# connector_valve.net
KiCad netlist of a schematic drawn in Altium Designer
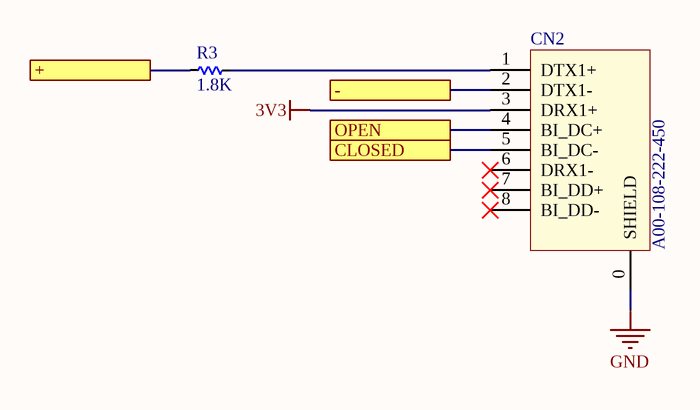
[diagram p0: connector_valve.SchDoc]

(export (version "E")
  (design (tool "Eeschema 10.0.6"))
  (components
    (comp (ref "CN2")
      (value "CONN_RJ45_TOP_A00-108-222-450")
      (footprint "RJ45 TOP ENTRY EDAC A00-108-222-450")
      (description "CONN, RJ-45, 1-PORT, 8-POS, VERT, 0.76um GOLD, TH")
      (fields (field (name "MFG") "EDAC Inc") (field (name "MFG P/N") "A00-108-222-450"))
      (libsource (lib "AltiumReleaseLibDB") (part "CONN_RJ45_TOP_A00-108-222-450"))
    )
    (comp (ref "R3")
      (value "1.8K")
      (footprint "R1206")
      (description "Resistor, 1.80K Ohms, 1206, 0.25W, ±1%")
      (fields (field (name "MFG") "YAGEO") (field (name "POWER") "1/4W"))
      (libsource (lib "AltiumReleaseLibDB") (part "__Template_Resistor"))
    )
  )
  (nets
    (net (code "1") (name "/+") (class "Default") (node (ref "R3") (pin "1") (pintype "passive")))
    (net (code "2") (name "/-") (class "Default")
      (node (ref "CN2") (pin "2") (pinfunction "DTX1-_2") (pintype "passive"))
    )
    (net (code "3") (name "/CLOSED") (class "Default")
      (node (ref "CN2") (pin "5") (pinfunction "BI_DC-_5") (pintype "passive"))
    )
    (net (code "4") (name "/OPEN") (class "Default")
      (node (ref "CN2") (pin "4") (pinfunction "BI_DC+_4") (pintype "passive"))
    )
    (net (code "5") (name "3V3") (class "Default")
      (node (ref "CN2") (pin "3") (pinfunction "DRX1+_3") (pintype "passive"))
    )
    (net (code "6") (name "GND") (class "Default")
      (node (ref "CN2") (pin "0") (pinfunction "SHIELD_0") (pintype "passive"))
    )
    (net (code "7") (name "Net-(CN2-DTX1+)") (class "Default")
      (node (ref "CN2") (pin "1") (pinfunction "DTX1+_1") (pintype "passive"))
      (node (ref "R3") (pin "2") (pintype "passive"))
    )
    (net (code "8") (name "unconnected-(CN2-BI_DD+-Pad7)") (class "Default")
      (node (ref "CN2") (pin "7") (pinfunction "BI_DD+_7") (pintype "passive+no_connect"))
    )
    (net (code "9") (name "unconnected-(CN2-BI_DD--Pad8)") (class "Default")
      (node (ref "CN2") (pin "8") (pinfunction "BI_DD-_8") (pintype "passive+no_connect"))
    )
    (net (code "10") (name "unconnected-(CN2-DRX1--Pad6)") (class "Default")
      (node (ref "CN2") (pin "6") (pinfunction "DRX1-_6") (pintype "passive+no_connect"))
    )
  )
)
